# BluePill.net
KiCad netlist of a schematic drawn in EAGLE
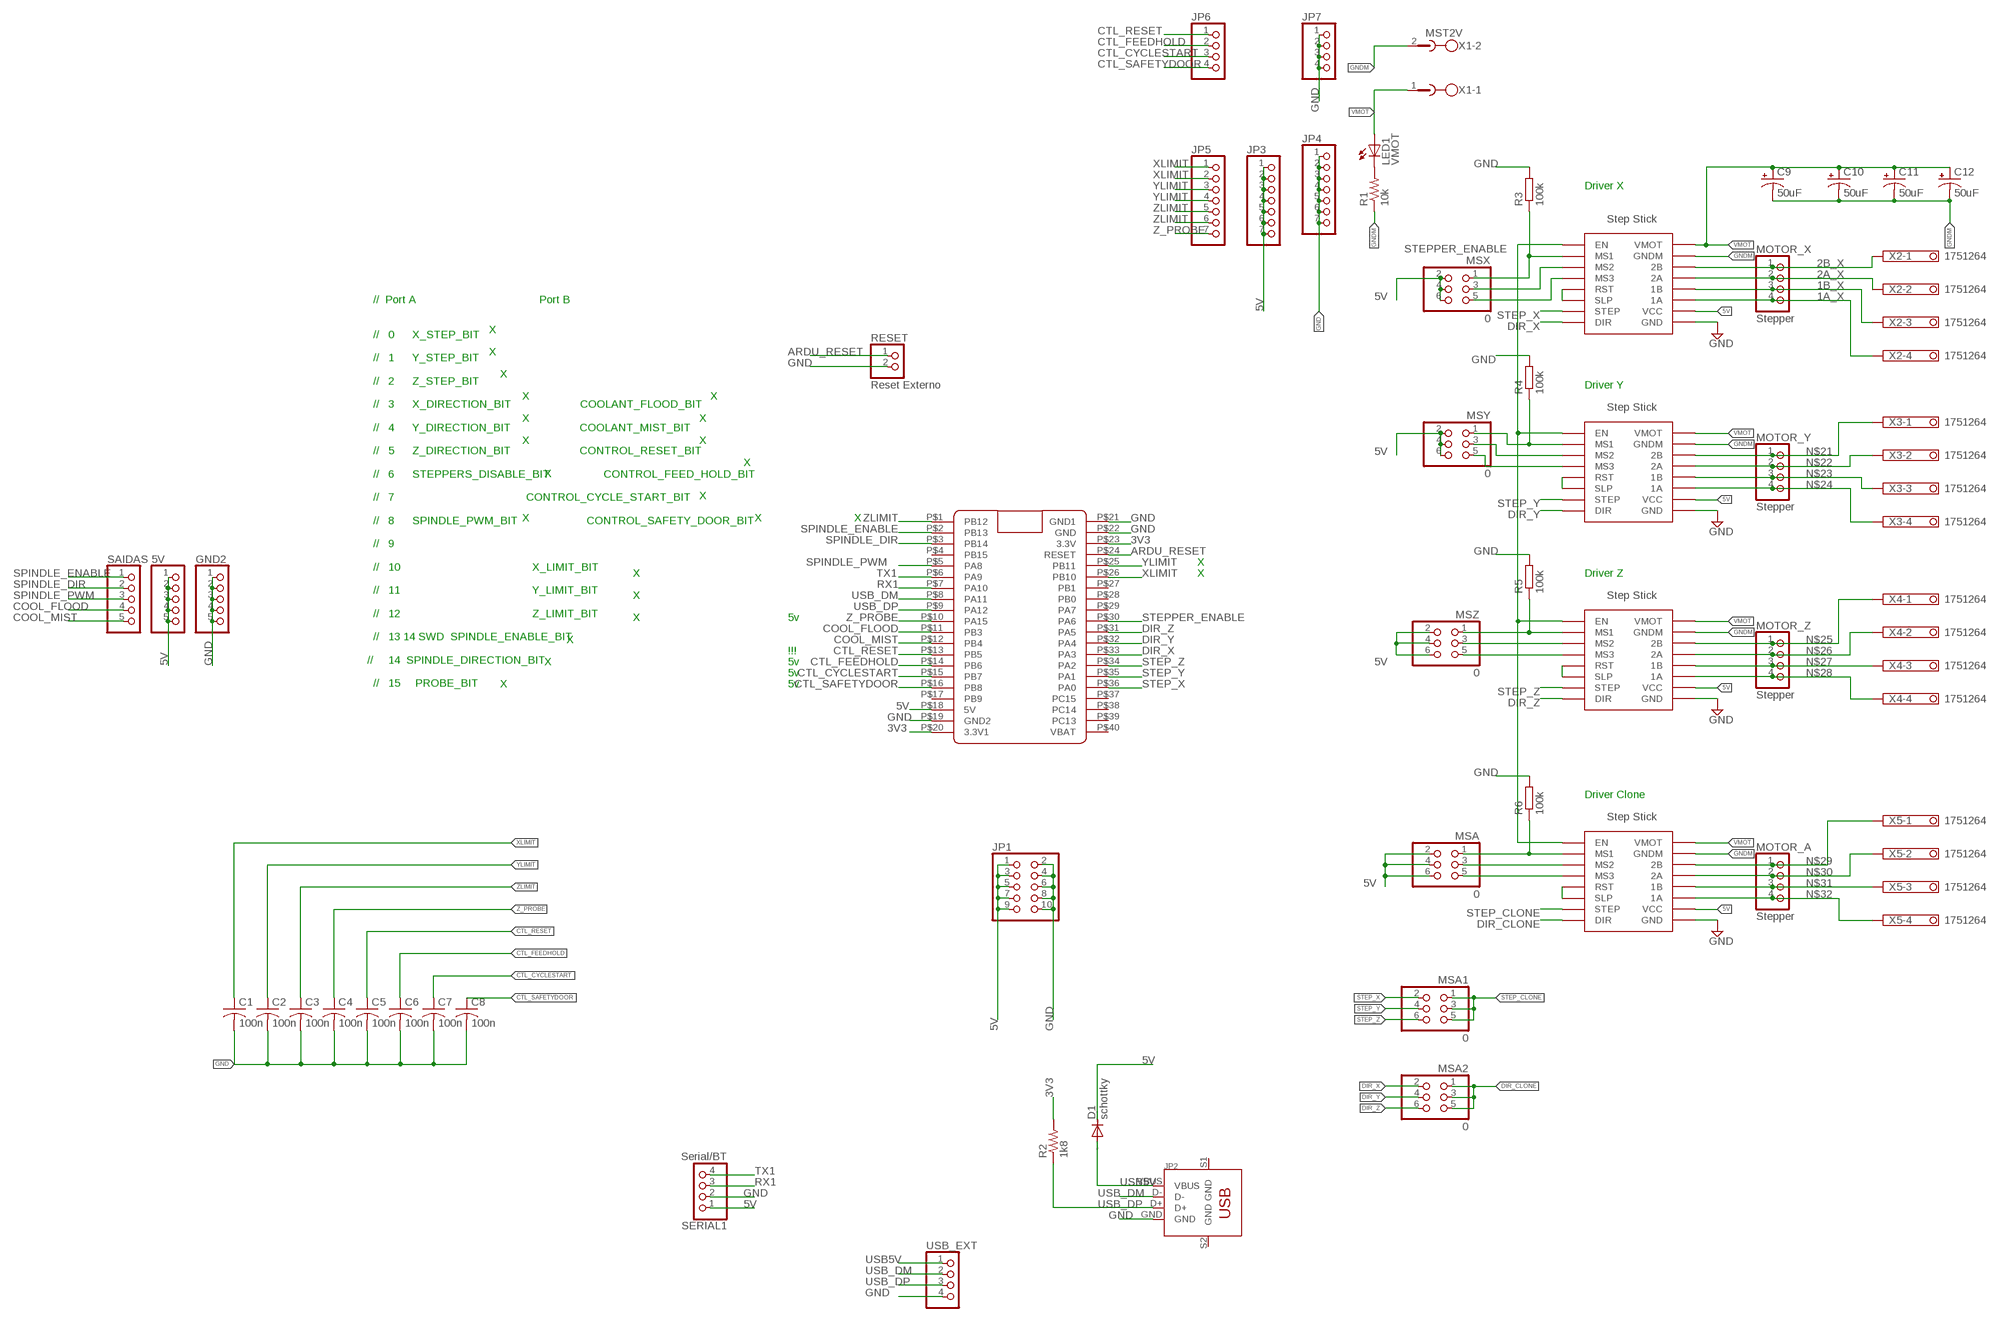
[diagram p0: schematic, sheet 1]

(export (version "E")
  (design (tool "Eeschema 10.0.6"))
  (components
    (comp (ref "5V")
      (value "PINHD-1X5")
      (footprint "eagle-import:1X05")
      (libsource (lib "eagle-import") (part "PINHD-1X5"))
    )
    (comp (ref "C1")
      (value "100n")
      (footprint "eagle-import:C0805K")
      (libsource (lib "eagle-import") (part "C-USC0805K"))
    )
    (comp (ref "C2")
      (value "100n")
      (footprint "eagle-import:C0805K")
      (libsource (lib "eagle-import") (part "C-USC0805K"))
    )
    (comp (ref "C3")
      (value "100n")
      (footprint "eagle-import:C0805K")
      (libsource (lib "eagle-import") (part "C-USC0805K"))
    )
    (comp (ref "C4")
      (value "100n")
      (footprint "eagle-import:C0805K")
      (libsource (lib "eagle-import") (part "C-USC0805K"))
    )
    (comp (ref "C5")
      (value "100n")
      (footprint "eagle-import:C0805K")
      (libsource (lib "eagle-import") (part "C-USC0805K"))
    )
    (comp (ref "C6")
      (value "100n")
      (footprint "eagle-import:C0805K")
      (libsource (lib "eagle-import") (part "C-USC0805K"))
    )
    (comp (ref "C7")
      (value "100n")
      (footprint "eagle-import:C0805K")
      (libsource (lib "eagle-import") (part "C-USC0805K"))
    )
    (comp (ref "C8")
      (value "100n")
      (footprint "eagle-import:C0805K")
      (libsource (lib "eagle-import") (part "C-USC0805K"))
    )
    (comp (ref "C9")
      (value "50uF")
      (footprint "eagle-import:TT5D9L")
      (libsource (lib "eagle-import") (part "CPOL-USTT5D9L"))
    )
    (comp (ref "C10")
      (value "50uF")
      (footprint "eagle-import:TT5D9L")
      (libsource (lib "eagle-import") (part "CPOL-USTT5D9L"))
    )
    (comp (ref "C11")
      (value "50uF")
      (footprint "eagle-import:TT5D9L")
      (libsource (lib "eagle-import") (part "CPOL-USTT5D9L"))
    )
    (comp (ref "C12")
      (value "50uF")
      (footprint "eagle-import:TT5D9L")
      (libsource (lib "eagle-import") (part "CPOL-USTT5D9L"))
    )
    (comp (ref "D1")
      (value "schottky")
      (footprint "eagle-import:DO-214AC")
      (libsource (lib "eagle-import") (part "DIODE-DO-214AC"))
    )
    (comp (ref "DRIVER_CLONE")
      (value "STEP-STICK")
      (footprint "eagle-import:STEP-STICK")
      (libsource (lib "eagle-import") (part "STEP-STICK"))
    )
    (comp (ref "DRIVER_X")
      (value "STEP-STICK")
      (footprint "eagle-import:STEP-STICK")
      (libsource (lib "eagle-import") (part "STEP-STICK"))
    )
    (comp (ref "DRIVER_Y")
      (value "STEP-STICK")
      (footprint "eagle-import:STEP-STICK")
      (libsource (lib "eagle-import") (part "STEP-STICK"))
    )
    (comp (ref "DRIVER_Z")
      (value "STEP-STICK")
      (footprint "eagle-import:STEP-STICK")
      (libsource (lib "eagle-import") (part "STEP-STICK"))
    )
    (comp (ref "GND2")
      (value "PINHD-1X5")
      (footprint "eagle-import:1X05")
      (libsource (lib "eagle-import") (part "PINHD-1X5"))
    )
    (comp (ref "JP1")
      (value "PINHD-2X5")
      (footprint "eagle-import:2X05")
      (libsource (lib "eagle-import") (part "PINHD-2X5"))
    )
    (comp (ref "JP2")
      (value "DIP-USB-B-TYPE-FMAL(4+2P-2.0-90D)")
      (footprint "eagle-import:USB4+2-2.5-90D-15.8X12MM")
      (libsource (lib "eagle-import") (part "DIP-USB-B-TYPE-FMAL(4+2P-2.0-90D)"))
    )
    (comp (ref "JP3")
      (value "PINHD-1X7")
      (footprint "eagle-import:1X07")
      (libsource (lib "eagle-import") (part "PINHD-1X7"))
    )
    (comp (ref "JP4")
      (value "PINHD-1X7")
      (footprint "eagle-import:1X07")
      (libsource (lib "eagle-import") (part "PINHD-1X7"))
    )
    (comp (ref "JP5")
      (value "PINHD-1X7")
      (footprint "eagle-import:1X07")
      (libsource (lib "eagle-import") (part "PINHD-1X7"))
    )
    (comp (ref "JP6")
      (value "PINHD-1X4")
      (footprint "eagle-import:1X04")
      (libsource (lib "eagle-import") (part "pinhead_325_PINHD-1X4"))
    )
    (comp (ref "JP7")
      (value "PINHD-1X4")
      (footprint "eagle-import:1X04")
      (libsource (lib "eagle-import") (part "pinhead_325_PINHD-1X4"))
    )
    (comp (ref "LED1")
      (value "VMOT")
      (footprint "eagle-import:CHIP-LED0805")
      (libsource (lib "eagle-import") (part "LEDCHIP-LED0805"))
    )
    (comp (ref "MOTOR_A")
      (value "Stepper")
      (footprint "eagle-import:1X04")
      (libsource (lib "eagle-import") (part "PINHD-1X4"))
    )
    (comp (ref "MOTOR_X")
      (value "Stepper")
      (footprint "eagle-import:1X04")
      (libsource (lib "eagle-import") (part "PINHD-1X4"))
    )
    (comp (ref "MOTOR_Y")
      (value "Stepper")
      (footprint "eagle-import:1X04")
      (libsource (lib "eagle-import") (part "PINHD-1X4"))
    )
    (comp (ref "MOTOR_Z")
      (value "Stepper")
      (footprint "eagle-import:1X04")
      (libsource (lib "eagle-import") (part "PINHD-1X4"))
    )
    (comp (ref "MSA")
      (value "0")
      (footprint "eagle-import:2X03")
      (libsource (lib "eagle-import") (part "PINHD-2X3"))
    )
    (comp (ref "MSA1")
      (value "0")
      (footprint "eagle-import:2X03")
      (libsource (lib "eagle-import") (part "PINHD-2X3"))
    )
    (comp (ref "MSA2")
      (value "0")
      (footprint "eagle-import:2X03")
      (libsource (lib "eagle-import") (part "PINHD-2X3"))
    )
    (comp (ref "MSX")
      (value "0")
      (footprint "eagle-import:2X03")
      (libsource (lib "eagle-import") (part "PINHD-2X3"))
    )
    (comp (ref "MSY")
      (value "0")
      (footprint "eagle-import:2X03")
      (libsource (lib "eagle-import") (part "PINHD-2X3"))
    )
    (comp (ref "MSZ")
      (value "0")
      (footprint "eagle-import:2X03")
      (libsource (lib "eagle-import") (part "PINHD-2X3"))
    )
    (comp (ref "R1")
      (value "10k")
      (footprint "eagle-import:M0805")
      (libsource (lib "eagle-import") (part "R-US_M0805"))
    )
    (comp (ref "R2")
      (value "1k8")
      (footprint "eagle-import:R0805")
      (libsource (lib "eagle-import") (part "resistor_348_R-US_R0805"))
    )
    (comp (ref "R3")
      (value "100k")
      (footprint "eagle-import:R0805")
      (libsource (lib "eagle-import") (part "R-EU_R0805"))
    )
    (comp (ref "R4")
      (value "100k")
      (footprint "eagle-import:R0805")
      (libsource (lib "eagle-import") (part "R-EU_R0805"))
    )
    (comp (ref "R5")
      (value "100k")
      (footprint "eagle-import:R0805")
      (libsource (lib "eagle-import") (part "R-EU_R0805"))
    )
    (comp (ref "R6")
      (value "100k")
      (footprint "eagle-import:R0805")
      (libsource (lib "eagle-import") (part "R-EU_R0805"))
    )
    (comp (ref "RESET")
      (value "Reset Externo")
      (footprint "eagle-import:1X02")
      (libsource (lib "eagle-import") (part "PINHD-1X2"))
    )
    (comp (ref "SAIDAS")
      (value "PINHD-1X5")
      (footprint "eagle-import:1X05")
      (libsource (lib "eagle-import") (part "PINHD-1X5"))
    )
    (comp (ref "SERIAL1")
      (value "Serial/BT")
      (footprint "eagle-import:1X04")
      (libsource (lib "eagle-import") (part "pinhead_325_PINHD-1X4"))
    )
    (comp (ref "U$1")
      (value "BLUE_PILL")
      (footprint "eagle-import:BLUE_PILL")
      (libsource (lib "eagle-import") (part "BLUE_PILL"))
    )
    (comp (ref "USB_EXT")
      (value "PINHD-1X4")
      (footprint "eagle-import:1X04")
      (libsource (lib "eagle-import") (part "pinhead_325_PINHD-1X4"))
    )
    (comp (ref "X1")
      (value "MST2V")
      (footprint "eagle-import:MSTBV2")
      (libsource (lib "eagle-import") (part "MST2V"))
    )
    (comp (ref "X2")
      (value "1751264")
      (footprint "eagle-import:1751264")
      (libsource (lib "eagle-import") (part "1751264"))
    )
    (comp (ref "X3")
      (value "1751264")
      (footprint "eagle-import:1751264")
      (libsource (lib "eagle-import") (part "1751264"))
    )
    (comp (ref "X4")
      (value "1751264")
      (footprint "eagle-import:1751264")
      (libsource (lib "eagle-import") (part "1751264"))
    )
    (comp (ref "X5")
      (value "1751264")
      (footprint "eagle-import:1751264")
      (libsource (lib "eagle-import") (part "1751264"))
    )
  )
  (nets
    (net (code "1") (name "/1A_X") (class "Default")
      (node (ref "DRIVER_X") (pin "1A") (pinfunction "1A_1A") (pintype "bidirectional"))
      (node (ref "MOTOR_X") (pin "4") (pinfunction "4_4") (pintype "passive"))
      (node (ref "X2") (pin "4") (pinfunction "K_4") (pintype "passive"))
    )
    (net (code "2") (name "/1B_X") (class "Default")
      (node (ref "DRIVER_X") (pin "1B") (pinfunction "1B_1B") (pintype "bidirectional"))
      (node (ref "MOTOR_X") (pin "3") (pinfunction "3_3") (pintype "passive"))
      (node (ref "X2") (pin "3") (pinfunction "K_3") (pintype "passive"))
    )
    (net (code "3") (name "/2A_X") (class "Default")
      (node (ref "DRIVER_X") (pin "2A") (pinfunction "2A_2A") (pintype "bidirectional"))
      (node (ref "MOTOR_X") (pin "2") (pinfunction "2_2") (pintype "passive"))
      (node (ref "X2") (pin "2") (pinfunction "K_2") (pintype "passive"))
    )
    (net (code "4") (name "/2B_X") (class "Default")
      (node (ref "DRIVER_X") (pin "2B") (pinfunction "2B_2B") (pintype "bidirectional"))
      (node (ref "MOTOR_X") (pin "1") (pinfunction "1_1") (pintype "passive"))
      (node (ref "X2") (pin "1") (pinfunction "K_1") (pintype "passive"))
    )
    (net (code "5") (name "/3V3") (class "Default")
      (node (ref "R2") (pin "2") (pinfunction "2_2") (pintype "passive"))
      (node (ref "U$1") (pin "P$20") (pinfunction "3.3V1_P$20") (pintype "bidirectional"))
      (node (ref "U$1") (pin "P$23") (pinfunction "3.3V_P$23") (pintype "bidirectional"))
    )
    (net (code "6") (name "/ARDU_RESET") (class "Default")
      (node (ref "RESET") (pin "1") (pinfunction "1_1") (pintype "passive"))
      (node (ref "U$1") (pin "P$24") (pinfunction "RESET_P$24") (pintype "bidirectional"))
    )
    (net (code "7") (name "/COOL_FLOOD") (class "Default")
      (node (ref "SAIDAS") (pin "4") (pinfunction "4_4") (pintype "passive"))
      (node (ref "U$1") (pin "P$11") (pinfunction "PB3_P$11") (pintype "bidirectional"))
    )
    (net (code "8") (name "/COOL_MIST") (class "Default")
      (node (ref "SAIDAS") (pin "5") (pinfunction "5_5") (pintype "passive"))
      (node (ref "U$1") (pin "P$12") (pinfunction "PB4_P$12") (pintype "bidirectional"))
    )
    (net (code "9") (name "/N$21") (class "Default")
      (node (ref "DRIVER_Y") (pin "2B") (pinfunction "2B_2B") (pintype "bidirectional"))
      (node (ref "MOTOR_Y") (pin "1") (pinfunction "1_1") (pintype "passive"))
      (node (ref "X3") (pin "1") (pinfunction "K_1") (pintype "passive"))
    )
    (net (code "10") (name "/N$22") (class "Default")
      (node (ref "DRIVER_Y") (pin "2A") (pinfunction "2A_2A") (pintype "bidirectional"))
      (node (ref "MOTOR_Y") (pin "2") (pinfunction "2_2") (pintype "passive"))
      (node (ref "X3") (pin "2") (pinfunction "K_2") (pintype "passive"))
    )
    (net (code "11") (name "/N$23") (class "Default")
      (node (ref "DRIVER_Y") (pin "1B") (pinfunction "1B_1B") (pintype "bidirectional"))
      (node (ref "MOTOR_Y") (pin "3") (pinfunction "3_3") (pintype "passive"))
      (node (ref "X3") (pin "3") (pinfunction "K_3") (pintype "passive"))
    )
    (net (code "12") (name "/N$24") (class "Default")
      (node (ref "DRIVER_Y") (pin "1A") (pinfunction "1A_1A") (pintype "bidirectional"))
      (node (ref "MOTOR_Y") (pin "4") (pinfunction "4_4") (pintype "passive"))
      (node (ref "X3") (pin "4") (pinfunction "K_4") (pintype "passive"))
    )
    (net (code "13") (name "/N$25") (class "Default")
      (node (ref "DRIVER_Z") (pin "2B") (pinfunction "2B_2B") (pintype "bidirectional"))
      (node (ref "MOTOR_Z") (pin "1") (pinfunction "1_1") (pintype "passive"))
      (node (ref "X4") (pin "1") (pinfunction "K_1") (pintype "passive"))
    )
    (net (code "14") (name "/N$26") (class "Default")
      (node (ref "DRIVER_Z") (pin "2A") (pinfunction "2A_2A") (pintype "bidirectional"))
      (node (ref "MOTOR_Z") (pin "2") (pinfunction "2_2") (pintype "passive"))
      (node (ref "X4") (pin "2") (pinfunction "K_2") (pintype "passive"))
    )
    (net (code "15") (name "/N$27") (class "Default")
      (node (ref "DRIVER_Z") (pin "1B") (pinfunction "1B_1B") (pintype "bidirectional"))
      (node (ref "MOTOR_Z") (pin "3") (pinfunction "3_3") (pintype "passive"))
      (node (ref "X4") (pin "3") (pinfunction "K_3") (pintype "passive"))
    )
    (net (code "16") (name "/N$28") (class "Default")
      (node (ref "DRIVER_Z") (pin "1A") (pinfunction "1A_1A") (pintype "bidirectional"))
      (node (ref "MOTOR_Z") (pin "4") (pinfunction "4_4") (pintype "passive"))
      (node (ref "X4") (pin "4") (pinfunction "K_4") (pintype "passive"))
    )
    (net (code "17") (name "/N$29") (class "Default")
      (node (ref "DRIVER_CLONE") (pin "2B") (pinfunction "2B_2B") (pintype "bidirectional"))
      (node (ref "MOTOR_A") (pin "1") (pinfunction "1_1") (pintype "passive"))
      (node (ref "X5") (pin "1") (pinfunction "K_1") (pintype "passive"))
    )
    (net (code "18") (name "/N$30") (class "Default")
      (node (ref "DRIVER_CLONE") (pin "2A") (pinfunction "2A_2A") (pintype "bidirectional"))
      (node (ref "MOTOR_A") (pin "2") (pinfunction "2_2") (pintype "passive"))
      (node (ref "X5") (pin "2") (pinfunction "K_2") (pintype "passive"))
    )
    (net (code "19") (name "/N$31") (class "Default")
      (node (ref "DRIVER_CLONE") (pin "1B") (pinfunction "1B_1B") (pintype "bidirectional"))
      (node (ref "MOTOR_A") (pin "3") (pinfunction "3_3") (pintype "passive"))
      (node (ref "X5") (pin "3") (pinfunction "K_3") (pintype "passive"))
    )
    (net (code "20") (name "/N$32") (class "Default")
      (node (ref "DRIVER_CLONE") (pin "1A") (pinfunction "1A_1A") (pintype "bidirectional"))
      (node (ref "MOTOR_A") (pin "4") (pinfunction "4_4") (pintype "passive"))
      (node (ref "X5") (pin "4") (pinfunction "K_4") (pintype "passive"))
    )
    (net (code "21") (name "/RX1") (class "Default")
      (node (ref "SERIAL1") (pin "3") (pinfunction "3_3") (pintype "passive"))
      (node (ref "U$1") (pin "P$7") (pinfunction "PA10_P$7") (pintype "bidirectional"))
    )
    (net (code "22") (name "/SPINDLE_DIR") (class "Default")
      (node (ref "SAIDAS") (pin "2") (pinfunction "2_2") (pintype "passive"))
      (node (ref "U$1") (pin "P$3") (pinfunction "PB14_P$3") (pintype "bidirectional"))
    )
    (net (code "23") (name "/SPINDLE_ENABLE") (class "Default")
      (node (ref "SAIDAS") (pin "1") (pinfunction "1_1") (pintype "passive"))
      (node (ref "U$1") (pin "P$2") (pinfunction "PB13_P$2") (pintype "bidirectional"))
    )
    (net (code "24") (name "/SPINDLE_PWM") (class "Default")
      (node (ref "SAIDAS") (pin "3") (pinfunction "3_3") (pintype "passive"))
      (node (ref "U$1") (pin "P$5") (pinfunction "PA8_P$5") (pintype "bidirectional"))
    )
    (net (code "25") (name "/STEPPER_ENABLE") (class "Default")
      (node (ref "DRIVER_CLONE") (pin "EN") (pinfunction "EN_EN") (pintype "bidirectional"))
      (node (ref "DRIVER_X") (pin "EN") (pinfunction "EN_EN") (pintype "bidirectional"))
      (node (ref "DRIVER_Y") (pin "EN") (pinfunction "EN_EN") (pintype "bidirectional"))
      (node (ref "DRIVER_Z") (pin "EN") (pinfunction "EN_EN") (pintype "bidirectional"))
      (node (ref "U$1") (pin "P$30") (pinfunction "PA6_P$30") (pintype "bidirectional"))
    )
    (net (code "26") (name "/TX1") (class "Default")
      (node (ref "SERIAL1") (pin "4") (pinfunction "4_4") (pintype "passive"))
      (node (ref "U$1") (pin "P$6") (pinfunction "PA9_P$6") (pintype "bidirectional"))
    )
    (net (code "27") (name "/USB5V") (class "Default")
      (node (ref "D1") (pin "A") (pinfunction "A_A") (pintype "passive"))
      (node (ref "JP2") (pin "VBUS") (pinfunction "VBUS_VBUS") (pintype "bidirectional"))
      (node (ref "USB_EXT") (pin "1") (pinfunction "1_1") (pintype "passive"))
    )
    (net (code "28") (name "/USB_DM") (class "Default")
      (node (ref "JP2") (pin "D-") (pinfunction "D-_D-") (pintype "bidirectional"))
      (node (ref "U$1") (pin "P$8") (pinfunction "PA11_P$8") (pintype "bidirectional"))
      (node (ref "USB_EXT") (pin "2") (pinfunction "2_2") (pintype "passive"))
    )
    (net (code "29") (name "/USB_DP") (class "Default")
      (node (ref "JP2") (pin "D+") (pinfunction "D+_D+") (pintype "bidirectional"))
      (node (ref "R2") (pin "1") (pinfunction "1_1") (pintype "passive"))
      (node (ref "U$1") (pin "P$9") (pinfunction "PA12_P$9") (pintype "bidirectional"))
      (node (ref "USB_EXT") (pin "3") (pinfunction "3_3") (pintype "passive"))
    )
    (net (code "30") (name "5V") (class "Default")
      (node (ref "5V") (pin "1") (pinfunction "1_1") (pintype "passive"))
      (node (ref "5V") (pin "2") (pinfunction "2_2") (pintype "passive"))
      (node (ref "5V") (pin "3") (pinfunction "3_3") (pintype "passive"))
      (node (ref "5V") (pin "4") (pinfunction "4_4") (pintype "passive"))
      (node (ref "5V") (pin "5") (pinfunction "5_5") (pintype "passive"))
      (node (ref "D1") (pin "C") (pinfunction "C_C") (pintype "passive"))
      (node (ref "DRIVER_CLONE") (pin "VCC") (pinfunction "VCC_VCC") (pintype "bidirectional"))
      (node (ref "DRIVER_X") (pin "VCC") (pinfunction "VCC_VCC") (pintype "bidirectional"))
      (node (ref "DRIVER_Y") (pin "VCC") (pinfunction "VCC_VCC") (pintype "bidirectional"))
      (node (ref "DRIVER_Z") (pin "VCC") (pinfunction "VCC_VCC") (pintype "bidirectional"))
      (node (ref "JP1") (pin "1") (pinfunction "1_1") (pintype "passive"))
      (node (ref "JP1") (pin "3") (pinfunction "3_3") (pintype "passive"))
      (node (ref "JP1") (pin "5") (pinfunction "5_5") (pintype "passive"))
      (node (ref "JP1") (pin "7") (pinfunction "7_7") (pintype "passive"))
      (node (ref "JP1") (pin "9") (pinfunction "9_9") (pintype "passive"))
      (node (ref "JP3") (pin "1") (pinfunction "1_1") (pintype "passive"))
      (node (ref "JP3") (pin "2") (pinfunction "2_2") (pintype "passive"))
      (node (ref "JP3") (pin "3") (pinfunction "3_3") (pintype "passive"))
      (node (ref "JP3") (pin "4") (pinfunction "4_4") (pintype "passive"))
      (node (ref "JP3") (pin "5") (pinfunction "5_5") (pintype "passive"))
      (node (ref "JP3") (pin "6") (pinfunction "6_6") (pintype "passive"))
      (node (ref "JP3") (pin "7") (pinfunction "7_7") (pintype "passive"))
      (node (ref "MSA") (pin "2") (pinfunction "2_2") (pintype "passive"))
      (node (ref "MSA") (pin "4") (pinfunction "4_4") (pintype "passive"))
      (node (ref "MSA") (pin "6") (pinfunction "6_6") (pintype "passive"))
      (node (ref "MSX") (pin "2") (pinfunction "2_2") (pintype "passive"))
      (node (ref "MSX") (pin "4") (pinfunction "4_4") (pintype "passive"))
      (node (ref "MSX") (pin "6") (pinfunction "6_6") (pintype "passive"))
      (node (ref "MSY") (pin "2") (pinfunction "2_2") (pintype "passive"))
      (node (ref "MSY") (pin "4") (pinfunction "4_4") (pintype "passive"))
      (node (ref "MSY") (pin "6") (pinfunction "6_6") (pintype "passive"))
      (node (ref "MSZ") (pin "2") (pinfunction "2_2") (pintype "passive"))
      (node (ref "MSZ") (pin "4") (pinfunction "4_4") (pintype "passive"))
      (node (ref "MSZ") (pin "6") (pinfunction "6_6") (pintype "passive"))
      (node (ref "SERIAL1") (pin "1") (pinfunction "1_1") (pintype "passive"))
      (node (ref "U$1") (pin "P$18") (pinfunction "5V_P$18") (pintype "bidirectional"))
    )
    (net (code "31") (name "CTL_CYCLESTART") (class "Default")
      (node (ref "C7") (pin "1") (pinfunction "1_1") (pintype "passive"))
      (node (ref "JP6") (pin "3") (pinfunction "3_3") (pintype "passive"))
      (node (ref "U$1") (pin "P$15") (pinfunction "PB7_P$15") (pintype "bidirectional"))
    )
    (net (code "32") (name "CTL_FEEDHOLD") (class "Default")
      (node (ref "C6") (pin "1") (pinfunction "1_1") (pintype "passive"))
      (node (ref "JP6") (pin "2") (pinfunction "2_2") (pintype "passive"))
      (node (ref "U$1") (pin "P$14") (pinfunction "PB6_P$14") (pintype "bidirectional"))
    )
    (net (code "33") (name "CTL_RESET") (class "Default")
      (node (ref "C5") (pin "1") (pinfunction "1_1") (pintype "passive"))
      (node (ref "JP6") (pin "1") (pinfunction "1_1") (pintype "passive"))
      (node (ref "U$1") (pin "P$13") (pinfunction "PB5_P$13") (pintype "bidirectional"))
    )
    (net (code "34") (name "CTL_SAFETYDOOR") (class "Default")
      (node (ref "C8") (pin "1") (pinfunction "1_1") (pintype "passive"))
      (node (ref "JP6") (pin "4") (pinfunction "4_4") (pintype "passive"))
      (node (ref "U$1") (pin "P$16") (pinfunction "PB8_P$16") (pintype "bidirectional"))
    )
    (net (code "35") (name "DIR_CLONE") (class "Default")
      (node (ref "DRIVER_CLONE") (pin "DIR") (pinfunction "DIR_DIR") (pintype "bidirectional"))
      (node (ref "MSA2") (pin "1") (pinfunction "1_1") (pintype "passive"))
      (node (ref "MSA2") (pin "3") (pinfunction "3_3") (pintype "passive"))
      (node (ref "MSA2") (pin "5") (pinfunction "5_5") (pintype "passive"))
    )
    (net (code "36") (name "DIR_X") (class "Default")
      (node (ref "DRIVER_X") (pin "DIR") (pinfunction "DIR_DIR") (pintype "bidirectional"))
      (node (ref "MSA2") (pin "2") (pinfunction "2_2") (pintype "passive"))
      (node (ref "U$1") (pin "P$33") (pinfunction "PA3_P$33") (pintype "bidirectional"))
    )
    (net (code "37") (name "DIR_Y") (class "Default")
      (node (ref "DRIVER_Y") (pin "DIR") (pinfunction "DIR_DIR") (pintype "bidirectional"))
      (node (ref "MSA2") (pin "4") (pinfunction "4_4") (pintype "passive"))
      (node (ref "U$1") (pin "P$32") (pinfunction "PA4_P$32") (pintype "bidirectional"))
    )
    (net (code "38") (name "DIR_Z") (class "Default")
      (node (ref "DRIVER_Z") (pin "DIR") (pinfunction "DIR_DIR") (pintype "bidirectional"))
      (node (ref "MSA2") (pin "6") (pinfunction "6_6") (pintype "passive"))
      (node (ref "U$1") (pin "P$31") (pinfunction "PA5_P$31") (pintype "bidirectional"))
    )
    (net (code "39") (name "GND") (class "Default")
      (node (ref "C1") (pin "2") (pinfunction "2_2") (pintype "passive"))
      (node (ref "C2") (pin "2") (pinfunction "2_2") (pintype "passive"))
      (node (ref "C3") (pin "2") (pinfunction "2_2") (pintype "passive"))
      (node (ref "C4") (pin "2") (pinfunction "2_2") (pintype "passive"))
      (node (ref "C5") (pin "2") (pinfunction "2_2") (pintype "passive"))
      (node (ref "C6") (pin "2") (pinfunction "2_2") (pintype "passive"))
      (node (ref "C7") (pin "2") (pinfunction "2_2") (pintype "passive"))
      (node (ref "C8") (pin "2") (pinfunction "2_2") (pintype "passive"))
      (node (ref "DRIVER_CLONE") (pin "GND") (pinfunction "GND_GND") (pintype "bidirectional"))
      (node (ref "DRIVER_X") (pin "GND") (pinfunction "GND_GND") (pintype "bidirectional"))
      (node (ref "DRIVER_Y") (pin "GND") (pinfunction "GND_GND") (pintype "bidirectional"))
      (node (ref "DRIVER_Z") (pin "GND") (pinfunction "GND_GND") (pintype "bidirectional"))
      (node (ref "GND2") (pin "1") (pinfunction "1_1") (pintype "passive"))
      (node (ref "GND2") (pin "2") (pinfunction "2_2") (pintype "passive"))
      (node (ref "GND2") (pin "3") (pinfunction "3_3") (pintype "passive"))
      (node (ref "GND2") (pin "4") (pinfunction "4_4") (pintype "passive"))
      (node (ref "GND2") (pin "5") (pinfunction "5_5") (pintype "passive"))
      (node (ref "JP1") (pin "10") (pinfunction "10_10") (pintype "passive"))
      (node (ref "JP1") (pin "2") (pinfunction "2_2") (pintype "passive"))
      (node (ref "JP1") (pin "4") (pinfunction "4_4") (pintype "passive"))
      (node (ref "JP1") (pin "6") (pinfunction "6_6") (pintype "passive"))
      (node (ref "JP1") (pin "8") (pinfunction "8_8") (pintype "passive"))
      (node (ref "JP2") (pin "GND") (pinfunction "GND_GND") (pintype "bidirectional"))
      (node (ref "JP4") (pin "1") (pinfunction "1_1") (pintype "passive"))
      (node (ref "JP4") (pin "2") (pinfunction "2_2") (pintype "passive"))
      (node (ref "JP4") (pin "3") (pinfunction "3_3") (pintype "passive"))
      (node (ref "JP4") (pin "4") (pinfunction "4_4") (pintype "passive"))
      (node (ref "JP4") (pin "5") (pinfunction "5_5") (pintype "passive"))
      (node (ref "JP4") (pin "6") (pinfunction "6_6") (pintype "passive"))
      (node (ref "JP4") (pin "7") (pinfunction "7_7") (pintype "passive"))
      (node (ref "JP7") (pin "1") (pinfunction "1_1") (pintype "passive"))
      (node (ref "JP7") (pin "2") (pinfunction "2_2") (pintype "passive"))
      (node (ref "JP7") (pin "3") (pinfunction "3_3") (pintype "passive"))
      (node (ref "JP7") (pin "4") (pinfunction "4_4") (pintype "passive"))
      (node (ref "R3") (pin "2") (pinfunction "2_2") (pintype "passive"))
      (node (ref "R4") (pin "2") (pinfunction "2_2") (pintype "passive"))
      (node (ref "R5") (pin "2") (pinfunction "2_2") (pintype "passive"))
      (node (ref "R6") (pin "2") (pinfunction "2_2") (pintype "passive"))
      (node (ref "RESET") (pin "2") (pinfunction "2_2") (pintype "passive"))
      (node (ref "SERIAL1") (pin "2") (pinfunction "2_2") (pintype "passive"))
      (node (ref "U$1") (pin "P$19") (pinfunction "GND2_P$19") (pintype "bidirectional"))
      (node (ref "U$1") (pin "P$21") (pinfunction "GND1_P$21") (pintype "power_in"))
      (node (ref "U$1") (pin "P$22") (pinfunction "GND_P$22") (pintype "bidirectional"))
      (node (ref "USB_EXT") (pin "4") (pinfunction "4_4") (pintype "passive"))
    )
    (net (code "40") (name "GNDM") (class "Default")
      (node (ref "C10") (pin "-") (pinfunction "-_-") (pintype "passive"))
      (node (ref "C11") (pin "-") (pinfunction "-_-") (pintype "passive"))
      (node (ref "C12") (pin "-") (pinfunction "-_-") (pintype "passive"))
      (node (ref "C9") (pin "-") (pinfunction "-_-") (pintype "passive"))
      (node (ref "DRIVER_CLONE") (pin "GNDM") (pinfunction "GNDM_GNDM") (pintype "bidirectional"))
      (node (ref "DRIVER_X") (pin "GNDM") (pinfunction "GNDM_GNDM") (pintype "bidirectional"))
      (node (ref "DRIVER_Y") (pin "GNDM") (pinfunction "GNDM_GNDM") (pintype "bidirectional"))
      (node (ref "DRIVER_Z") (pin "GNDM") (pinfunction "GNDM_GNDM") (pintype "bidirectional"))
      (node (ref "R1") (pin "1") (pinfunction "1_1") (pintype "passive"))
      (node (ref "X1") (pin "2") (pinfunction "1_2") (pintype "passive"))
    )
    (net (code "41") (name "Net-(DRIVER_CLONE-PadMS1)") (class "Default")
      (node (ref "DRIVER_CLONE") (pin "MS1") (pinfunction "MS1_MS1") (pintype "bidirectional"))
      (node (ref "MSA") (pin "1") (pinfunction "1_1") (pintype "passive"))
      (node (ref "R6") (pin "1") (pinfunction "1_1") (pintype "passive"))
    )
    (net (code "42") (name "Net-(DRIVER_CLONE-PadMS2)") (class "Default")
      (node (ref "DRIVER_CLONE") (pin "MS2") (pinfunction "MS2_MS2") (pintype "bidirectional"))
      (node (ref "MSA") (pin "3") (pinfunction "3_3") (pintype "passive"))
    )
    (net (code "43") (name "Net-(DRIVER_CLONE-PadMS3)") (class "Default")
      (node (ref "DRIVER_CLONE") (pin "MS3") (pinfunction "MS3_MS3") (pintype "bidirectional"))
      (node (ref "MSA") (pin "5") (pinfunction "5_5") (pintype "passive"))
    )
    (net (code "44") (name "Net-(DRIVER_CLONE-PadRST)") (class "Default")
      (node (ref "DRIVER_CLONE") (pin "RST") (pinfunction "RST_RST") (pintype "bidirectional"))
      (node (ref "DRIVER_CLONE") (pin "SLP") (pinfunction "SLP_SLP") (pintype "bidirectional"))
    )
    (net (code "45") (name "Net-(DRIVER_X-PadMS1)") (class "Default")
      (node (ref "DRIVER_X") (pin "MS1") (pinfunction "MS1_MS1") (pintype "bidirectional"))
      (node (ref "MSX") (pin "1") (pinfunction "1_1") (pintype "passive"))
      (node (ref "R3") (pin "1") (pinfunction "1_1") (pintype "passive"))
    )
    (net (code "46") (name "Net-(DRIVER_X-PadMS2)") (class "Default")
      (node (ref "DRIVER_X") (pin "MS2") (pinfunction "MS2_MS2") (pintype "bidirectional"))
      (node (ref "MSX") (pin "3") (pinfunction "3_3") (pintype "passive"))
    )
    (net (code "47") (name "Net-(DRIVER_X-PadMS3)") (class "Default")
      (node (ref "DRIVER_X") (pin "MS3") (pinfunction "MS3_MS3") (pintype "bidirectional"))
      (node (ref "MSX") (pin "5") (pinfunction "5_5") (pintype "passive"))
    )
    (net (code "48") (name "Net-(DRIVER_X-PadRST)") (class "Default")
      (node (ref "DRIVER_X") (pin "RST") (pinfunction "RST_RST") (pintype "bidirectional"))
      (node (ref "DRIVER_X") (pin "SLP") (pinfunction "SLP_SLP") (pintype "bidirectional"))
    )
    (net (code "49") (name "Net-(DRIVER_Y-PadMS1)") (class "Default")
      (node (ref "DRIVER_Y") (pin "MS1") (pinfunction "MS1_MS1") (pintype "bidirectional"))
      (node (ref "MSY") (pin "1") (pinfunction "1_1") (pintype "passive"))
      (node (ref "R4") (pin "1") (pinfunction "1_1") (pintype "passive"))
    )
    (net (code "50") (name "Net-(DRIVER_Y-PadMS2)") (class "Default")
      (node (ref "DRIVER_Y") (pin "MS2") (pinfunction "MS2_MS2") (pintype "bidirectional"))
      (node (ref "MSY") (pin "3") (pinfunction "3_3") (pintype "passive"))
    )
    (net (code "51") (name "Net-(DRIVER_Y-PadMS3)") (class "Default")
      (node (ref "DRIVER_Y") (pin "MS3") (pinfunction "MS3_MS3") (pintype "bidirectional"))
      (node (ref "MSY") (pin "5") (pinfunction "5_5") (pintype "passive"))
    )
    (net (code "52") (name "Net-(DRIVER_Y-PadRST)") (class "Default")
      (node (ref "DRIVER_Y") (pin "RST") (pinfunction "RST_RST") (pintype "bidirectional"))
      (node (ref "DRIVER_Y") (pin "SLP") (pinfunction "SLP_SLP") (pintype "bidirectional"))
    )
    (net (code "53") (name "Net-(DRIVER_Z-PadMS1)") (class "Default")
      (node (ref "DRIVER_Z") (pin "MS1") (pinfunction "MS1_MS1") (pintype "bidirectional"))
      (node (ref "MSZ") (pin "1") (pinfunction "1_1") (pintype "passive"))
      (node (ref "R5") (pin "1") (pinfunction "1_1") (pintype "passive"))
    )
    (net (code "54") (name "Net-(DRIVER_Z-PadMS2)") (class "Default")
      (node (ref "DRIVER_Z") (pin "MS2") (pinfunction "MS2_MS2") (pintype "bidirectional"))
      (node (ref "MSZ") (pin "3") (pinfunction "3_3") (pintype "passive"))
    )
    (net (code "55") (name "Net-(DRIVER_Z-PadMS3)") (class "Default")
      (node (ref "DRIVER_Z") (pin "MS3") (pinfunction "MS3_MS3") (pintype "bidirectional"))
      (node (ref "MSZ") (pin "5") (pinfunction "5_5") (pintype "passive"))
    )
    (net (code "56") (name "Net-(DRIVER_Z-PadRST)") (class "Default")
      (node (ref "DRIVER_Z") (pin "RST") (pinfunction "RST_RST") (pintype "bidirectional"))
      (node (ref "DRIVER_Z") (pin "SLP") (pinfunction "SLP_SLP") (pintype "bidirectional"))
    )
    (net (code "57") (name "Net-(LED1-PadC)") (class "Default")
      (node (ref "LED1") (pin "C") (pinfunction "C_C") (pintype "passive"))
      (node (ref "R1") (pin "2") (pinfunction "2_2") (pintype "passive"))
    )
    (net (code "58") (name "STEP_CLONE") (class "Default")
      (node (ref "DRIVER_CLONE") (pin "SPT") (pinfunction "STEP_SPT") (pintype "bidirectional"))
      (node (ref "MSA1") (pin "1") (pinfunction "1_1") (pintype "passive"))
      (node (ref "MSA1") (pin "3") (pinfunction "3_3") (pintype "passive"))
      (node (ref "MSA1") (pin "5") (pinfunction "5_5") (pintype "passive"))
    )
    (net (code "59") (name "STEP_X") (class "Default")
      (node (ref "DRIVER_X") (pin "SPT") (pinfunction "STEP_SPT") (pintype "bidirectional"))
      (node (ref "MSA1") (pin "2") (pinfunction "2_2") (pintype "passive"))
      (node (ref "U$1") (pin "P$36") (pinfunction "PA0_P$36") (pintype "bidirectional"))
    )
    (net (code "60") (name "STEP_Y") (class "Default")
      (node (ref "DRIVER_Y") (pin "SPT") (pinfunction "STEP_SPT") (pintype "bidirectional"))
      (node (ref "MSA1") (pin "4") (pinfunction "4_4") (pintype "passive"))
      (node (ref "U$1") (pin "P$35") (pinfunction "PA1_P$35") (pintype "bidirectional"))
    )
    (net (code "61") (name "STEP_Z") (class "Default")
      (node (ref "DRIVER_Z") (pin "SPT") (pinfunction "STEP_SPT") (pintype "bidirectional"))
      (node (ref "MSA1") (pin "6") (pinfunction "6_6") (pintype "passive"))
      (node (ref "U$1") (pin "P$34") (pinfunction "PA2_P$34") (pintype "bidirectional"))
    )
    (net (code "62") (name "VMOT") (class "Default")
      (node (ref "C10") (pin "+") (pinfunction "+_+") (pintype "passive"))
      (node (ref "C11") (pin "+") (pinfunction "+_+") (pintype "passive"))
      (node (ref "C12") (pin "+") (pinfunction "+_+") (pintype "passive"))
      (node (ref "C9") (pin "+") (pinfunction "+_+") (pintype "passive"))
      (node (ref "DRIVER_CLONE") (pin "VMOT") (pinfunction "VMOT_VMOT") (pintype "bidirectional"))
      (node (ref "DRIVER_X") (pin "VMOT") (pinfunction "VMOT_VMOT") (pintype "bidirectional"))
      (node (ref "DRIVER_Y") (pin "VMOT") (pinfunction "VMOT_VMOT") (pintype "bidirectional"))
      (node (ref "DRIVER_Z") (pin "VMOT") (pinfunction "VMOT_VMOT") (pintype "bidirectional"))
      (node (ref "LED1") (pin "A") (pinfunction "A_A") (pintype "passive"))
      (node (ref "X1") (pin "1") (pinfunction "1_1") (pintype "passive"))
    )
    (net (code "63") (name "XLIMIT") (class "Default")
      (node (ref "C1") (pin "1") (pinfunction "1_1") (pintype "passive"))
      (node (ref "JP5") (pin "1") (pinfunction "1_1") (pintype "passive"))
      (node (ref "JP5") (pin "2") (pinfunction "2_2") (pintype "passive"))
      (node (ref "U$1") (pin "P$26") (pinfunction "PB10_P$26") (pintype "bidirectional"))
    )
    (net (code "64") (name "YLIMIT") (class "Default")
      (node (ref "C2") (pin "1") (pinfunction "1_1") (pintype "passive"))
      (node (ref "JP5") (pin "3") (pinfunction "3_3") (pintype "passive"))
      (node (ref "JP5") (pin "4") (pinfunction "4_4") (pintype "passive"))
      (node (ref "U$1") (pin "P$25") (pinfunction "PB11_P$25") (pintype "bidirectional"))
    )
    (net (code "65") (name "ZLIMIT") (class "Default")
      (node (ref "C3") (pin "1") (pinfunction "1_1") (pintype "passive"))
      (node (ref "JP5") (pin "5") (pinfunction "5_5") (pintype "passive"))
      (node (ref "JP5") (pin "6") (pinfunction "6_6") (pintype "passive"))
      (node (ref "U$1") (pin "P$1") (pinfunction "PB12_P$1") (pintype "bidirectional"))
    )
    (net (code "66") (name "Z_PROBE") (class "Default")
      (node (ref "C4") (pin "1") (pinfunction "1_1") (pintype "passive"))
      (node (ref "JP5") (pin "7") (pinfunction "7_7") (pintype "passive"))
      (node (ref "U$1") (pin "P$10") (pinfunction "PA15_P$10") (pintype "bidirectional"))
    )
    (net (code "67") (name "unconnected-(JP2-GND-PadS1)") (class "Default")
      (node (ref "JP2") (pin "S1") (pinfunction "GND_S1") (pintype "bidirectional"))
    )
    (net (code "68") (name "unconnected-(JP2-GND-PadS2)") (class "Default")
      (node (ref "JP2") (pin "S2") (pinfunction "GND_S2") (pintype "bidirectional"))
    )
    (net (code "69") (name "unconnected-(U$1-PA7-PadP$29)") (class "Default")
      (node (ref "U$1") (pin "P$29") (pinfunction "PA7_P$29") (pintype "bidirectional"))
    )
    (net (code "70") (name "unconnected-(U$1-PB0-PadP$28)") (class "Default")
      (node (ref "U$1") (pin "P$28") (pinfunction "PB0_P$28") (pintype "bidirectional"))
    )
    (net (code "71") (name "unconnected-(U$1-PB1-PadP$27)") (class "Default")
      (node (ref "U$1") (pin "P$27") (pinfunction "PB1_P$27") (pintype "bidirectional"))
    )
    (net (code "72") (name "unconnected-(U$1-PB9-PadP$17)") (class "Default")
      (node (ref "U$1") (pin "P$17") (pinfunction "PB9_P$17") (pintype "bidirectional"))
    )
    (net (code "73") (name "unconnected-(U$1-PB15-PadP$4)") (class "Default")
      (node (ref "U$1") (pin "P$4") (pinfunction "PB15_P$4") (pintype "bidirectional"))
    )
    (net (code "74") (name "unconnected-(U$1-PC13-PadP$39)") (class "Default")
      (node (ref "U$1") (pin "P$39") (pinfunction "PC13_P$39") (pintype "bidirectional"))
    )
    (net (code "75") (name "unconnected-(U$1-PC14-PadP$38)") (class "Default")
      (node (ref "U$1") (pin "P$38") (pinfunction "PC14_P$38") (pintype "bidirectional"))
    )
    (net (code "76") (name "unconnected-(U$1-PC15-PadP$37)") (class "Default")
      (node (ref "U$1") (pin "P$37") (pinfunction "PC15_P$37") (pintype "bidirectional"))
    )
    (net (code "77") (name "unconnected-(U$1-VBAT-PadP$40)") (class "Default")
      (node (ref "U$1") (pin "P$40") (pinfunction "VBAT_P$40") (pintype "bidirectional"))
    )
  )
)
